# BelaExpander.net
KiCad netlist of a schematic drawn in EAGLE
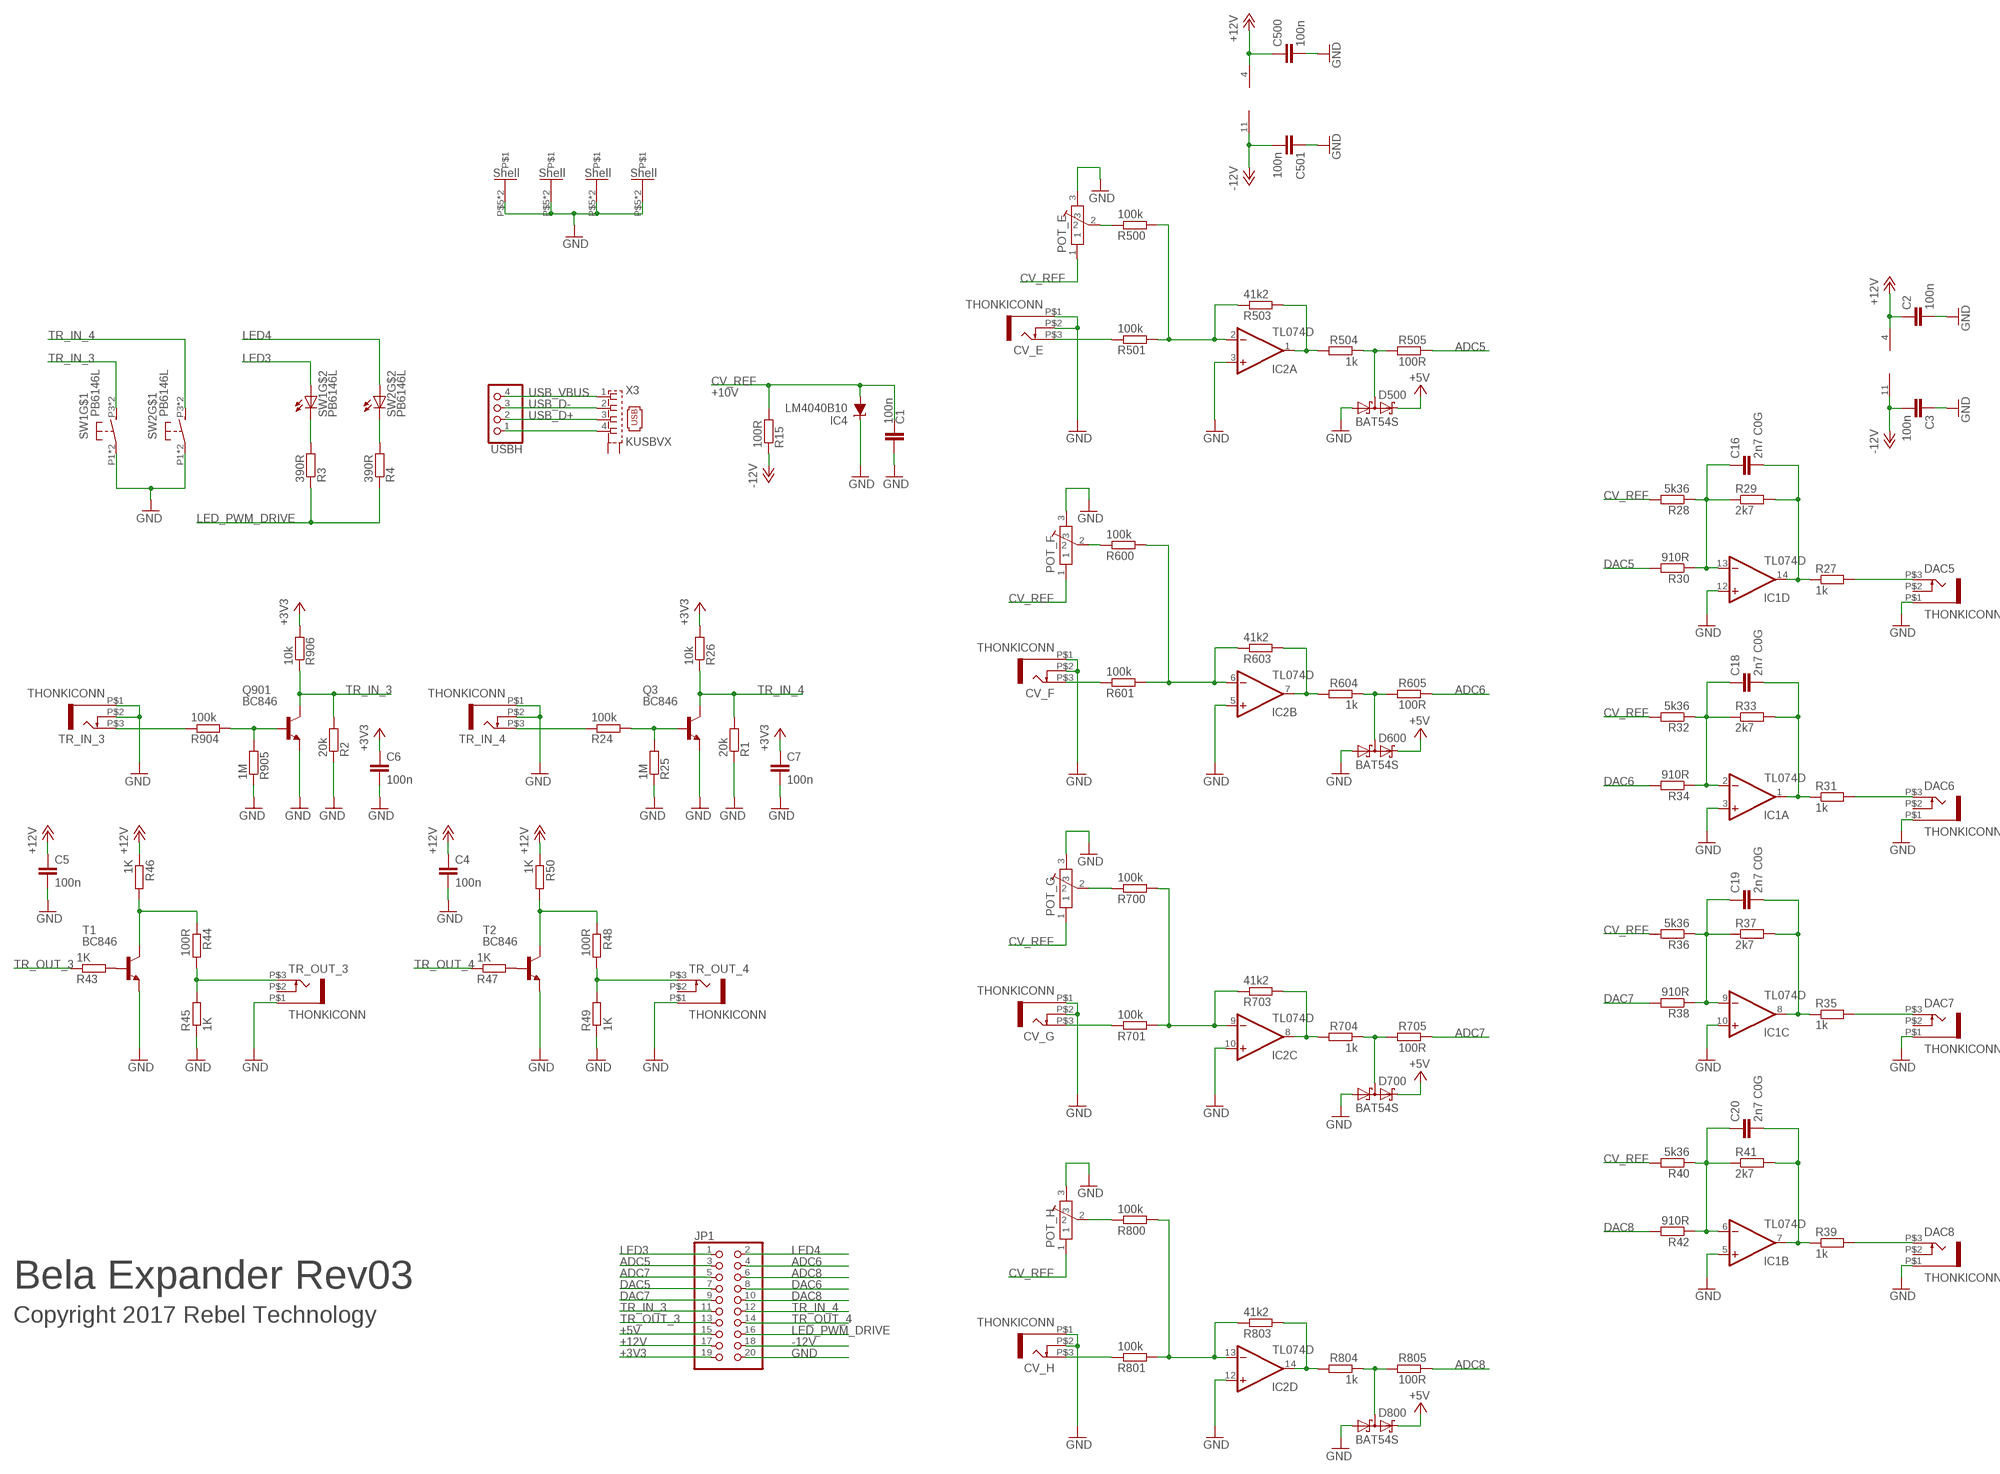
[diagram p0: schematic, sheet 1]

(export (version "E")
  (design (tool "Eeschema 10.0.6"))
  (components
    (comp (ref "C1")
      (value "100n")
      (footprint "eagle-import:C0603")
      (libsource (lib "eagle-import") (part "resistor_C-EUC0603"))
    )
    (comp (ref "C2")
      (value "100n")
      (footprint "eagle-import:C0603")
      (libsource (lib "eagle-import") (part "resistor_C-EUC0603"))
    )
    (comp (ref "C3")
      (value "100n")
      (footprint "eagle-import:C0603")
      (libsource (lib "eagle-import") (part "resistor_C-EUC0603"))
    )
    (comp (ref "C4")
      (value "100n")
      (footprint "eagle-import:C0603")
      (libsource (lib "eagle-import") (part "resistor_C-EUC0603"))
    )
    (comp (ref "C5")
      (value "100n")
      (footprint "eagle-import:C0603")
      (libsource (lib "eagle-import") (part "resistor_C-EUC0603"))
    )
    (comp (ref "C6")
      (value "100n")
      (footprint "eagle-import:C0603")
      (libsource (lib "eagle-import") (part "resistor_C-EUC0603"))
    )
    (comp (ref "C7")
      (value "100n")
      (footprint "eagle-import:C0603")
      (libsource (lib "eagle-import") (part "resistor_C-EUC0603"))
    )
    (comp (ref "C16")
      (value "2n7 C0G")
      (footprint "eagle-import:C0603")
      (libsource (lib "eagle-import") (part "C-EUC0603"))
    )
    (comp (ref "C18")
      (value "2n7 C0G")
      (footprint "eagle-import:C0603")
      (libsource (lib "eagle-import") (part "C-EUC0603"))
    )
    (comp (ref "C19")
      (value "2n7 C0G")
      (footprint "eagle-import:C0603")
      (libsource (lib "eagle-import") (part "C-EUC0603"))
    )
    (comp (ref "C20")
      (value "2n7 C0G")
      (footprint "eagle-import:C0603")
      (libsource (lib "eagle-import") (part "C-EUC0603"))
    )
    (comp (ref "C500")
      (value "100n")
      (footprint "eagle-import:C0603")
      (libsource (lib "eagle-import") (part "resistor_C-EUC0603"))
    )
    (comp (ref "C501")
      (value "100n")
      (footprint "eagle-import:C0603")
      (libsource (lib "eagle-import") (part "resistor_C-EUC0603"))
    )
    (comp (ref "CV_E")
      (value "THONKICONN")
      (footprint "eagle-import:THONKICONN")
      (libsource (lib "eagle-import") (part "THONKICONN"))
    )
    (comp (ref "CV_F")
      (value "THONKICONN")
      (footprint "eagle-import:THONKICONN")
      (libsource (lib "eagle-import") (part "THONKICONN"))
    )
    (comp (ref "CV_G")
      (value "THONKICONN")
      (footprint "eagle-import:THONKICONN")
      (libsource (lib "eagle-import") (part "THONKICONN"))
    )
    (comp (ref "CV_H")
      (value "THONKICONN")
      (footprint "eagle-import:THONKICONN")
      (libsource (lib "eagle-import") (part "THONKICONN"))
    )
    (comp (ref "D500")
      (value "BAT54S")
      (footprint "eagle-import:SOT23")
      (libsource (lib "eagle-import") (part "BAT54S"))
    )
    (comp (ref "D600")
      (value "BAT54S")
      (footprint "eagle-import:SOT23")
      (libsource (lib "eagle-import") (part "BAT54S"))
    )
    (comp (ref "D700")
      (value "BAT54S")
      (footprint "eagle-import:SOT23")
      (libsource (lib "eagle-import") (part "BAT54S"))
    )
    (comp (ref "D800")
      (value "BAT54S")
      (footprint "eagle-import:SOT23")
      (libsource (lib "eagle-import") (part "BAT54S"))
    )
    (comp (ref "DAC5")
      (value "THONKICONN")
      (footprint "eagle-import:THONKICONN")
      (libsource (lib "eagle-import") (part "THONKICONN"))
    )
    (comp (ref "DAC6")
      (value "THONKICONN")
      (footprint "eagle-import:THONKICONN")
      (libsource (lib "eagle-import") (part "THONKICONN"))
    )
    (comp (ref "DAC7")
      (value "THONKICONN")
      (footprint "eagle-import:THONKICONN")
      (libsource (lib "eagle-import") (part "THONKICONN"))
    )
    (comp (ref "DAC8")
      (value "THONKICONN")
      (footprint "eagle-import:THONKICONN")
      (libsource (lib "eagle-import") (part "THONKICONN"))
    )
    (comp (ref "IC1")
      (value "TL074D")
      (footprint "eagle-import:SO14")
      (libsource (lib "eagle-import") (part "TL074D"))
    )
    (comp (ref "IC2")
      (value "TL074D")
      (footprint "eagle-import:SO14")
      (libsource (lib "eagle-import") (part "TL074D"))
    )
    (comp (ref "IC4")
      (value "LM4040B10")
      (footprint "eagle-import:DBZ_R-PDSO-G3")
      (fields (field (name "MF") "TEXAS INSTRUMENT CONNECTORS") (field (name "MPN") "LM4041C12QDBZT"))
      (libsource (lib "eagle-import") (part "LM4041DBZC12"))
    )
    (comp (ref "JP1")
      (value "PINHD-2X10")
      (footprint "eagle-import:2X10")
      (libsource (lib "eagle-import") (part "PINHD-2X10"))
    )
    (comp (ref "POT_E")
      (value "POT-ALPS-RK09L1140")
      (footprint "eagle-import:POT-ALPS-RK09L1140")
      (libsource (lib "eagle-import") (part "POT-ALPS-RK09L1140"))
    )
    (comp (ref "POT_F")
      (value "POT-ALPS-RK09L1140")
      (footprint "eagle-import:POT-ALPS-RK09L1140")
      (libsource (lib "eagle-import") (part "POT-ALPS-RK09L1140"))
    )
    (comp (ref "POT_G")
      (value "POT-ALPS-RK09L1140")
      (footprint "eagle-import:POT-ALPS-RK09L1140")
      (libsource (lib "eagle-import") (part "POT-ALPS-RK09L1140"))
    )
    (comp (ref "POT_H")
      (value "POT-ALPS-RK09L1140")
      (footprint "eagle-import:POT-ALPS-RK09L1140")
      (libsource (lib "eagle-import") (part "POT-ALPS-RK09L1140"))
    )
    (comp (ref "Q3")
      (value "BC846")
      (footprint "eagle-import:SOT23")
      (libsource (lib "eagle-import") (part "BC846"))
    )
    (comp (ref "Q901")
      (value "BC846")
      (footprint "eagle-import:SOT23")
      (libsource (lib "eagle-import") (part "BC846"))
    )
    (comp (ref "R1")
      (value "20k")
      (footprint "eagle-import:0603")
      (libsource (lib "eagle-import") (part "R-EU_0603"))
    )
    (comp (ref "R2")
      (value "20k")
      (footprint "eagle-import:0603")
      (libsource (lib "eagle-import") (part "R-EU_0603"))
    )
    (comp (ref "R3")
      (value "390R")
      (footprint "eagle-import:0603")
      (libsource (lib "eagle-import") (part "R-EU_0603"))
    )
    (comp (ref "R4")
      (value "390R")
      (footprint "eagle-import:0603")
      (libsource (lib "eagle-import") (part "R-EU_0603"))
    )
    (comp (ref "R15")
      (value "100R")
      (footprint "eagle-import:0603")
      (libsource (lib "eagle-import") (part "R-EU_0603"))
    )
    (comp (ref "R24")
      (value "100k")
      (footprint "eagle-import:0603")
      (libsource (lib "eagle-import") (part "R-EU_0603"))
    )
    (comp (ref "R25")
      (value "1M")
      (footprint "eagle-import:0603")
      (libsource (lib "eagle-import") (part "R-EU_0603"))
    )
    (comp (ref "R26")
      (value "10k")
      (footprint "eagle-import:0603")
      (libsource (lib "eagle-import") (part "R-EU_0603"))
    )
    (comp (ref "R27")
      (value "1k")
      (footprint "eagle-import:0603")
      (libsource (lib "eagle-import") (part "R-EU_0603"))
    )
    (comp (ref "R28")
      (value "5k36")
      (footprint "eagle-import:0603")
      (libsource (lib "eagle-import") (part "R-EU_0603"))
    )
    (comp (ref "R29")
      (value "2k7")
      (footprint "eagle-import:0603")
      (libsource (lib "eagle-import") (part "R-EU_0603"))
    )
    (comp (ref "R30")
      (value "910R")
      (footprint "eagle-import:0603")
      (libsource (lib "eagle-import") (part "R-EU_0603"))
    )
    (comp (ref "R31")
      (value "1k")
      (footprint "eagle-import:0603")
      (libsource (lib "eagle-import") (part "R-EU_0603"))
    )
    (comp (ref "R32")
      (value "5k36")
      (footprint "eagle-import:0603")
      (libsource (lib "eagle-import") (part "R-EU_0603"))
    )
    (comp (ref "R33")
      (value "2k7")
      (footprint "eagle-import:0603")
      (libsource (lib "eagle-import") (part "R-EU_0603"))
    )
    (comp (ref "R34")
      (value "910R")
      (footprint "eagle-import:0603")
      (libsource (lib "eagle-import") (part "R-EU_0603"))
    )
    (comp (ref "R35")
      (value "1k")
      (footprint "eagle-import:0603")
      (libsource (lib "eagle-import") (part "R-EU_0603"))
    )
    (comp (ref "R36")
      (value "5k36")
      (footprint "eagle-import:0603")
      (libsource (lib "eagle-import") (part "R-EU_0603"))
    )
    (comp (ref "R37")
      (value "2k7")
      (footprint "eagle-import:0603")
      (libsource (lib "eagle-import") (part "R-EU_0603"))
    )
    (comp (ref "R38")
      (value "910R")
      (footprint "eagle-import:0603")
      (libsource (lib "eagle-import") (part "R-EU_0603"))
    )
    (comp (ref "R39")
      (value "1k")
      (footprint "eagle-import:0603")
      (libsource (lib "eagle-import") (part "R-EU_0603"))
    )
    (comp (ref "R40")
      (value "5k36")
      (footprint "eagle-import:0603")
      (libsource (lib "eagle-import") (part "R-EU_0603"))
    )
    (comp (ref "R41")
      (value "2k7")
      (footprint "eagle-import:0603")
      (libsource (lib "eagle-import") (part "R-EU_0603"))
    )
    (comp (ref "R42")
      (value "910R")
      (footprint "eagle-import:0603")
      (libsource (lib "eagle-import") (part "R-EU_0603"))
    )
    (comp (ref "R43")
      (value "1K")
      (footprint "eagle-import:0603")
      (libsource (lib "eagle-import") (part "R-EU_0603"))
    )
    (comp (ref "R44")
      (value "100R")
      (footprint "eagle-import:0603")
      (libsource (lib "eagle-import") (part "R-EU_0603"))
    )
    (comp (ref "R45")
      (value "1K")
      (footprint "eagle-import:0603")
      (libsource (lib "eagle-import") (part "R-EU_0603"))
    )
    (comp (ref "R46")
      (value "1K")
      (footprint "eagle-import:0603")
      (libsource (lib "eagle-import") (part "R-EU_0603"))
    )
    (comp (ref "R47")
      (value "1K")
      (footprint "eagle-import:0603")
      (libsource (lib "eagle-import") (part "R-EU_0603"))
    )
    (comp (ref "R48")
      (value "100R")
      (footprint "eagle-import:0603")
      (libsource (lib "eagle-import") (part "R-EU_0603"))
    )
    (comp (ref "R49")
      (value "1K")
      (footprint "eagle-import:0603")
      (libsource (lib "eagle-import") (part "R-EU_0603"))
    )
    (comp (ref "R50")
      (value "1K")
      (footprint "eagle-import:0603")
      (libsource (lib "eagle-import") (part "R-EU_0603"))
    )
    (comp (ref "R500")
      (value "100k")
      (footprint "eagle-import:0603")
      (libsource (lib "eagle-import") (part "R-EU_0603"))
    )
    (comp (ref "R501")
      (value "100k")
      (footprint "eagle-import:0603")
      (libsource (lib "eagle-import") (part "R-EU_0603"))
    )
    (comp (ref "R503")
      (value "41k2")
      (footprint "eagle-import:0603")
      (libsource (lib "eagle-import") (part "R-EU_0603"))
    )
    (comp (ref "R504")
      (value "1k")
      (footprint "eagle-import:0603")
      (libsource (lib "eagle-import") (part "R-EU_0603"))
    )
    (comp (ref "R505")
      (value "100R")
      (footprint "eagle-import:0603")
      (libsource (lib "eagle-import") (part "R-EU_0603"))
    )
    (comp (ref "R600")
      (value "100k")
      (footprint "eagle-import:0603")
      (libsource (lib "eagle-import") (part "R-EU_0603"))
    )
    (comp (ref "R601")
      (value "100k")
      (footprint "eagle-import:0603")
      (libsource (lib "eagle-import") (part "R-EU_0603"))
    )
    (comp (ref "R603")
      (value "41k2")
      (footprint "eagle-import:0603")
      (libsource (lib "eagle-import") (part "R-EU_0603"))
    )
    (comp (ref "R604")
      (value "1k")
      (footprint "eagle-import:0603")
      (libsource (lib "eagle-import") (part "R-EU_0603"))
    )
    (comp (ref "R605")
      (value "100R")
      (footprint "eagle-import:0603")
      (libsource (lib "eagle-import") (part "R-EU_0603"))
    )
    (comp (ref "R700")
      (value "100k")
      (footprint "eagle-import:0603")
      (libsource (lib "eagle-import") (part "R-EU_0603"))
    )
    (comp (ref "R701")
      (value "100k")
      (footprint "eagle-import:0603")
      (libsource (lib "eagle-import") (part "R-EU_0603"))
    )
    (comp (ref "R703")
      (value "41k2")
      (footprint "eagle-import:0603")
      (libsource (lib "eagle-import") (part "R-EU_0603"))
    )
    (comp (ref "R704")
      (value "1k")
      (footprint "eagle-import:0603")
      (libsource (lib "eagle-import") (part "R-EU_0603"))
    )
    (comp (ref "R705")
      (value "100R")
      (footprint "eagle-import:0603")
      (libsource (lib "eagle-import") (part "R-EU_0603"))
    )
    (comp (ref "R800")
      (value "100k")
      (footprint "eagle-import:0603")
      (libsource (lib "eagle-import") (part "R-EU_0603"))
    )
    (comp (ref "R801")
      (value "100k")
      (footprint "eagle-import:0603")
      (libsource (lib "eagle-import") (part "R-EU_0603"))
    )
    (comp (ref "R803")
      (value "41k2")
      (footprint "eagle-import:0603")
      (libsource (lib "eagle-import") (part "R-EU_0603"))
    )
    (comp (ref "R804")
      (value "1k")
      (footprint "eagle-import:0603")
      (libsource (lib "eagle-import") (part "R-EU_0603"))
    )
    (comp (ref "R805")
      (value "100R")
      (footprint "eagle-import:0603")
      (libsource (lib "eagle-import") (part "R-EU_0603"))
    )
    (comp (ref "R904")
      (value "100k")
      (footprint "eagle-import:0603")
      (libsource (lib "eagle-import") (part "R-EU_0603"))
    )
    (comp (ref "R905")
      (value "1M")
      (footprint "eagle-import:0603")
      (libsource (lib "eagle-import") (part "R-EU_0603"))
    )
    (comp (ref "R906")
      (value "10k")
      (footprint "eagle-import:0603")
      (libsource (lib "eagle-import") (part "R-EU_0603"))
    )
    (comp (ref "SW1")
      (value "PB6146L")
      (footprint "eagle-import:PB6146L")
      (libsource (lib "eagle-import") (part "PB6146L"))
    )
    (comp (ref "SW2")
      (value "PB6146L")
      (footprint "eagle-import:PB6146L")
      (libsource (lib "eagle-import") (part "PB6146L"))
    )
    (comp (ref "T1")
      (value "BC846")
      (footprint "eagle-import:SOT23")
      (libsource (lib "eagle-import") (part "BC846"))
    )
    (comp (ref "T2")
      (value "BC846")
      (footprint "eagle-import:SOT23")
      (libsource (lib "eagle-import") (part "BC846"))
    )
    (comp (ref "TR_IN_3")
      (value "THONKICONN")
      (footprint "eagle-import:THONKICONN")
      (libsource (lib "eagle-import") (part "THONKICONN"))
    )
    (comp (ref "TR_IN_4")
      (value "THONKICONN")
      (footprint "eagle-import:THONKICONN")
      (libsource (lib "eagle-import") (part "THONKICONN"))
    )
    (comp (ref "TR_OUT_3")
      (value "THONKICONN")
      (footprint "eagle-import:THONKICONN")
      (libsource (lib "eagle-import") (part "THONKICONN"))
    )
    (comp (ref "TR_OUT_4")
      (value "THONKICONN")
      (footprint "eagle-import:THONKICONN")
      (libsource (lib "eagle-import") (part "THONKICONN"))
    )
    (comp (ref "USBH")
      (value "PINHD-1X4")
      (footprint "eagle-import:1X04")
      (libsource (lib "eagle-import") (part "PINHD-1X4"))
    )
    (comp (ref "X3")
      (value "KUSBVX")
      (footprint "eagle-import:KUSBVX")
      (libsource (lib "eagle-import") (part "KUSBVX"))
    )
  )
  (nets
    (net (code "1") (name "+3V3") (class "Default")
      (node (ref "C6") (pin "1") (pinfunction "1_1") (pintype "passive"))
      (node (ref "C7") (pin "1") (pinfunction "1_1") (pintype "passive"))
      (node (ref "JP1") (pin "19") (pinfunction "19_19") (pintype "passive"))
      (node (ref "R26") (pin "2") (pinfunction "2_2") (pintype "passive"))
      (node (ref "R906") (pin "2") (pinfunction "2_2") (pintype "passive"))
    )
    (net (code "2") (name "+5V") (class "Default")
      (node (ref "D500") (pin "2") (pinfunction "C2_2") (pintype "passive"))
      (node (ref "D600") (pin "2") (pinfunction "C2_2") (pintype "passive"))
      (node (ref "D700") (pin "2") (pinfunction "C2_2") (pintype "passive"))
      (node (ref "D800") (pin "2") (pinfunction "C2_2") (pintype "passive"))
      (node (ref "JP1") (pin "15") (pinfunction "15_15") (pintype "passive"))
    )
    (net (code "3") (name "+12V") (class "Default")
      (node (ref "C2") (pin "1") (pinfunction "1_1") (pintype "passive"))
      (node (ref "C4") (pin "1") (pinfunction "1_1") (pintype "passive"))
      (node (ref "C5") (pin "1") (pinfunction "1_1") (pintype "passive"))
      (node (ref "C500") (pin "1") (pinfunction "1_1") (pintype "passive"))
      (node (ref "IC1") (pin "4") (pinfunction "V+_4") (pintype "power_in"))
      (node (ref "IC2") (pin "4") (pinfunction "V+_4") (pintype "power_in"))
      (node (ref "JP1") (pin "17") (pinfunction "17_17") (pintype "passive"))
      (node (ref "R46") (pin "1") (pinfunction "1_1") (pintype "passive"))
      (node (ref "R50") (pin "1") (pinfunction "1_1") (pintype "passive"))
    )
    (net (code "4") (name "-12V") (class "Default")
      (node (ref "C3") (pin "2") (pinfunction "2_2") (pintype "passive"))
      (node (ref "C501") (pin "2") (pinfunction "2_2") (pintype "passive"))
      (node (ref "IC1") (pin "11") (pinfunction "V-_11") (pintype "power_in"))
      (node (ref "IC2") (pin "11") (pinfunction "V-_11") (pintype "power_in"))
      (node (ref "JP1") (pin "18") (pinfunction "18_18") (pintype "passive"))
      (node (ref "R15") (pin "1") (pinfunction "1_1") (pintype "passive"))
    )
    (net (code "5") (name "/ADC5") (class "Default")
      (node (ref "JP1") (pin "3") (pinfunction "3_3") (pintype "passive"))
      (node (ref "R505") (pin "1") (pinfunction "1_1") (pintype "passive"))
    )
    (net (code "6") (name "/ADC6") (class "Default")
      (node (ref "JP1") (pin "4") (pinfunction "4_4") (pintype "passive"))
      (node (ref "R605") (pin "1") (pinfunction "1_1") (pintype "passive"))
    )
    (net (code "7") (name "/ADC7") (class "Default")
      (node (ref "JP1") (pin "5") (pinfunction "5_5") (pintype "passive"))
      (node (ref "R705") (pin "1") (pinfunction "1_1") (pintype "passive"))
    )
    (net (code "8") (name "/ADC8") (class "Default")
      (node (ref "JP1") (pin "6") (pinfunction "6_6") (pintype "passive"))
      (node (ref "R805") (pin "1") (pinfunction "1_1") (pintype "passive"))
    )
    (net (code "9") (name "/CV_REF") (class "Default")
      (node (ref "C1") (pin "1") (pinfunction "1_1") (pintype "passive"))
      (node (ref "IC4") (pin "2") (pinfunction "A_2") (pintype "passive"))
      (node (ref "POT_E") (pin "1") (pinfunction "1_1") (pintype "bidirectional"))
      (node (ref "POT_F") (pin "1") (pinfunction "1_1") (pintype "bidirectional"))
      (node (ref "POT_G") (pin "1") (pinfunction "1_1") (pintype "bidirectional"))
      (node (ref "POT_H") (pin "1") (pinfunction "1_1") (pintype "bidirectional"))
      (node (ref "R15") (pin "2") (pinfunction "2_2") (pintype "passive"))
      (node (ref "R28") (pin "2") (pinfunction "2_2") (pintype "passive"))
      (node (ref "R32") (pin "2") (pinfunction "2_2") (pintype "passive"))
      (node (ref "R36") (pin "2") (pinfunction "2_2") (pintype "passive"))
      (node (ref "R40") (pin "2") (pinfunction "2_2") (pintype "passive"))
    )
    (net (code "10") (name "/DAC5") (class "Default")
      (node (ref "JP1") (pin "7") (pinfunction "7_7") (pintype "passive"))
      (node (ref "R30") (pin "2") (pinfunction "2_2") (pintype "passive"))
    )
    (net (code "11") (name "/DAC6") (class "Default")
      (node (ref "JP1") (pin "8") (pinfunction "8_8") (pintype "passive"))
      (node (ref "R34") (pin "2") (pinfunction "2_2") (pintype "passive"))
    )
    (net (code "12") (name "/DAC7") (class "Default")
      (node (ref "JP1") (pin "9") (pinfunction "9_9") (pintype "passive"))
      (node (ref "R38") (pin "2") (pinfunction "2_2") (pintype "passive"))
    )
    (net (code "13") (name "/DAC8") (class "Default")
      (node (ref "JP1") (pin "10") (pinfunction "10_10") (pintype "passive"))
      (node (ref "R42") (pin "2") (pinfunction "2_2") (pintype "passive"))
    )
    (net (code "14") (name "/LED3") (class "Default")
      (node (ref "JP1") (pin "1") (pinfunction "1_1") (pintype "passive"))
      (node (ref "SW1") (pin "PL1") (pinfunction "A_PL1") (pintype "passive"))
    )
    (net (code "15") (name "/LED4") (class "Default")
      (node (ref "JP1") (pin "2") (pinfunction "2_2") (pintype "passive"))
      (node (ref "SW2") (pin "PL1") (pinfunction "A_PL1") (pintype "passive"))
    )
    (net (code "16") (name "/LED_PWM_DRIVE") (class "Default")
      (node (ref "JP1") (pin "16") (pinfunction "16_16") (pintype "passive"))
      (node (ref "R3") (pin "1") (pinfunction "1_1") (pintype "passive"))
      (node (ref "R4") (pin "1") (pinfunction "1_1") (pintype "passive"))
    )
    (net (code "17") (name "/TR_IN_3") (class "Default")
      (node (ref "JP1") (pin "11") (pinfunction "11_11") (pintype "passive"))
      (node (ref "Q901") (pin "3") (pinfunction "C_3") (pintype "passive"))
      (node (ref "R2") (pin "2") (pinfunction "2_2") (pintype "passive"))
      (node (ref "R906") (pin "1") (pinfunction "1_1") (pintype "passive"))
      (node (ref "SW1") (pin "P3") (pinfunction "S_P3") (pintype "passive"))
      (node (ref "SW1") (pin "P4") (pinfunction "S_P4") (pintype "passive"))
    )
    (net (code "18") (name "/TR_IN_4") (class "Default")
      (node (ref "JP1") (pin "12") (pinfunction "12_12") (pintype "passive"))
      (node (ref "Q3") (pin "3") (pinfunction "C_3") (pintype "passive"))
      (node (ref "R1") (pin "2") (pinfunction "2_2") (pintype "passive"))
      (node (ref "R26") (pin "1") (pinfunction "1_1") (pintype "passive"))
      (node (ref "SW2") (pin "P3") (pinfunction "S_P3") (pintype "passive"))
      (node (ref "SW2") (pin "P4") (pinfunction "S_P4") (pintype "passive"))
    )
    (net (code "19") (name "/TR_OUT_3") (class "Default")
      (node (ref "JP1") (pin "13") (pinfunction "13_13") (pintype "passive"))
      (node (ref "R43") (pin "1") (pinfunction "1_1") (pintype "passive"))
    )
    (net (code "20") (name "/TR_OUT_4") (class "Default")
      (node (ref "JP1") (pin "14") (pinfunction "14_14") (pintype "passive"))
      (node (ref "R47") (pin "1") (pinfunction "1_1") (pintype "passive"))
    )
    (net (code "21") (name "/USB_D+") (class "Default")
      (node (ref "USBH") (pin "2") (pinfunction "2_2") (pintype "passive"))
      (node (ref "X3") (pin "3") (pinfunction "3_3") (pintype "passive"))
    )
    (net (code "22") (name "/USB_D-") (class "Default")
      (node (ref "USBH") (pin "3") (pinfunction "3_3") (pintype "passive"))
      (node (ref "X3") (pin "2") (pinfunction "2_2") (pintype "passive"))
    )
    (net (code "23") (name "/USB_VBUS") (class "Default")
      (node (ref "USBH") (pin "4") (pinfunction "4_4") (pintype "passive"))
      (node (ref "X3") (pin "1") (pinfunction "1_1") (pintype "passive"))
    )
    (net (code "24") (name "GND") (class "Default")
      (node (ref "C1") (pin "2") (pinfunction "2_2") (pintype "passive"))
      (node (ref "C2") (pin "2") (pinfunction "2_2") (pintype "passive"))
      (node (ref "C3") (pin "1") (pinfunction "1_1") (pintype "passive"))
      (node (ref "C4") (pin "2") (pinfunction "2_2") (pintype "passive"))
      (node (ref "C5") (pin "2") (pinfunction "2_2") (pintype "passive"))
      (node (ref "C500") (pin "2") (pinfunction "2_2") (pintype "passive"))
      (node (ref "C501") (pin "1") (pinfunction "1_1") (pintype "passive"))
      (node (ref "C6") (pin "2") (pinfunction "2_2") (pintype "passive"))
      (node (ref "C7") (pin "2") (pinfunction "2_2") (pintype "passive"))
      (node (ref "CV_E") (pin "P$1") (pinfunction "5_P$1") (pintype "passive"))
      (node (ref "CV_E") (pin "P$2") (pinfunction "4_P$2") (pintype "passive"))
      (node (ref "CV_F") (pin "P$1") (pinfunction "5_P$1") (pintype "passive"))
      (node (ref "CV_F") (pin "P$2") (pinfunction "4_P$2") (pintype "passive"))
      (node (ref "CV_G") (pin "P$1") (pinfunction "5_P$1") (pintype "passive"))
      (node (ref "CV_G") (pin "P$2") (pinfunction "4_P$2") (pintype "passive"))
      (node (ref "CV_H") (pin "P$1") (pinfunction "5_P$1") (pintype "passive"))
      (node (ref "CV_H") (pin "P$2") (pinfunction "4_P$2") (pintype "passive"))
      (node (ref "D500") (pin "1") (pinfunction "A1_1") (pintype "passive"))
      (node (ref "D600") (pin "1") (pinfunction "A1_1") (pintype "passive"))
      (node (ref "D700") (pin "1") (pinfunction "A1_1") (pintype "passive"))
      (node (ref "D800") (pin "1") (pinfunction "A1_1") (pintype "passive"))
      (node (ref "DAC5") (pin "P$1") (pinfunction "5_P$1") (pintype "passive"))
      (node (ref "DAC6") (pin "P$1") (pinfunction "5_P$1") (pintype "passive"))
      (node (ref "DAC7") (pin "P$1") (pinfunction "5_P$1") (pintype "passive"))
      (node (ref "DAC8") (pin "P$1") (pinfunction "5_P$1") (pintype "passive"))
      (node (ref "IC1") (pin "10") (pinfunction "+IN_10") (pintype "input"))
      (node (ref "IC1") (pin "12") (pinfunction "+IN_12") (pintype "input"))
      (node (ref "IC1") (pin "3") (pinfunction "+IN_3") (pintype "input"))
      (node (ref "IC1") (pin "5") (pinfunction "+IN_5") (pintype "input"))
      (node (ref "IC2") (pin "10") (pinfunction "+IN_10") (pintype "input"))
      (node (ref "IC2") (pin "12") (pinfunction "+IN_12") (pintype "input"))
      (node (ref "IC2") (pin "3") (pinfunction "+IN_3") (pintype "input"))
      (node (ref "IC2") (pin "5") (pinfunction "+IN_5") (pintype "input"))
      (node (ref "IC4") (pin "1") (pinfunction "C_1") (pintype "passive"))
      (node (ref "JP1") (pin "20") (pinfunction "20_20") (pintype "passive"))
      (node (ref "POT_E") (pin "3") (pinfunction "3_3") (pintype "bidirectional"))
      (node (ref "POT_E") (pin "P$5") (pinfunction "P$1_P$5") (pintype "bidirectional"))
      (node (ref "POT_E") (pin "P$6") (pinfunction "P$1_P$6") (pintype "bidirectional"))
      (node (ref "POT_F") (pin "3") (pinfunction "3_3") (pintype "bidirectional"))
      (node (ref "POT_F") (pin "P$5") (pinfunction "P$1_P$5") (pintype "bidirectional"))
      (node (ref "POT_F") (pin "P$6") (pinfunction "P$1_P$6") (pintype "bidirectional"))
      (node (ref "POT_G") (pin "3") (pinfunction "3_3") (pintype "bidirectional"))
      (node (ref "POT_G") (pin "P$5") (pinfunction "P$1_P$5") (pintype "bidirectional"))
      (node (ref "POT_G") (pin "P$6") (pinfunction "P$1_P$6") (pintype "bidirectional"))
      (node (ref "POT_H") (pin "3") (pinfunction "3_3") (pintype "bidirectional"))
      (node (ref "POT_H") (pin "P$5") (pinfunction "P$1_P$5") (pintype "bidirectional"))
      (node (ref "POT_H") (pin "P$6") (pinfunction "P$1_P$6") (pintype "bidirectional"))
      (node (ref "Q3") (pin "2") (pinfunction "E_2") (pintype "passive"))
      (node (ref "Q901") (pin "2") (pinfunction "E_2") (pintype "passive"))
      (node (ref "R1") (pin "1") (pinfunction "1_1") (pintype "passive"))
      (node (ref "R2") (pin "1") (pinfunction "1_1") (pintype "passive"))
      (node (ref "R25") (pin "1") (pinfunction "1_1") (pintype "passive"))
      (node (ref "R45") (pin "1") (pinfunction "1_1") (pintype "passive"))
      (node (ref "R49") (pin "1") (pinfunction "1_1") (pintype "passive"))
      (node (ref "R905") (pin "1") (pinfunction "1_1") (pintype "passive"))
      (node (ref "SW1") (pin "P1") (pinfunction "P_P1") (pintype "passive"))
      (node (ref "SW1") (pin "P2") (pinfunction "P_P2") (pintype "passive"))
      (node (ref "SW2") (pin "P1") (pinfunction "P_P1") (pintype "passive"))
      (node (ref "SW2") (pin "P2") (pinfunction "P_P2") (pintype "passive"))
      (node (ref "T1") (pin "2") (pinfunction "E_2") (pintype "passive"))
      (node (ref "T2") (pin "2") (pinfunction "E_2") (pintype "passive"))
      (node (ref "TR_IN_3") (pin "P$1") (pinfunction "5_P$1") (pintype "passive"))
      (node (ref "TR_IN_3") (pin "P$2") (pinfunction "4_P$2") (pintype "passive"))
      (node (ref "TR_IN_4") (pin "P$1") (pinfunction "5_P$1") (pintype "passive"))
      (node (ref "TR_IN_4") (pin "P$2") (pinfunction "4_P$2") (pintype "passive"))
      (node (ref "TR_OUT_3") (pin "P$1") (pinfunction "5_P$1") (pintype "passive"))
      (node (ref "TR_OUT_4") (pin "P$1") (pinfunction "5_P$1") (pintype "passive"))
    )
    (net (code "25") (name "Net-(CV_E-3)") (class "Default")
      (node (ref "CV_E") (pin "P$3") (pinfunction "3_P$3") (pintype "passive"))
      (node (ref "R501") (pin "1") (pinfunction "1_1") (pintype "passive"))
    )
    (net (code "26") (name "Net-(CV_F-3)") (class "Default")
      (node (ref "CV_F") (pin "P$3") (pinfunction "3_P$3") (pintype "passive"))
      (node (ref "R601") (pin "1") (pinfunction "1_1") (pintype "passive"))
    )
    (net (code "27") (name "Net-(CV_G-3)") (class "Default")
      (node (ref "CV_G") (pin "P$3") (pinfunction "3_P$3") (pintype "passive"))
      (node (ref "R701") (pin "1") (pinfunction "1_1") (pintype "passive"))
    )
    (net (code "28") (name "Net-(CV_H-3)") (class "Default")
      (node (ref "CV_H") (pin "P$3") (pinfunction "3_P$3") (pintype "passive"))
      (node (ref "R801") (pin "1") (pinfunction "1_1") (pintype "passive"))
    )
    (net (code "29") (name "Net-(D500-C1A2)") (class "Default")
      (node (ref "D500") (pin "3") (pinfunction "C1A2_3") (pintype "passive"))
      (node (ref "R504") (pin "1") (pinfunction "1_1") (pintype "passive"))
      (node (ref "R505") (pin "2") (pinfunction "2_2") (pintype "passive"))
    )
    (net (code "30") (name "Net-(D600-C1A2)") (class "Default")
      (node (ref "D600") (pin "3") (pinfunction "C1A2_3") (pintype "passive"))
      (node (ref "R604") (pin "1") (pinfunction "1_1") (pintype "passive"))
      (node (ref "R605") (pin "2") (pinfunction "2_2") (pintype "passive"))
    )
    (net (code "31") (name "Net-(D700-C1A2)") (class "Default")
      (node (ref "D700") (pin "3") (pinfunction "C1A2_3") (pintype "passive"))
      (node (ref "R704") (pin "1") (pinfunction "1_1") (pintype "passive"))
      (node (ref "R705") (pin "2") (pinfunction "2_2") (pintype "passive"))
    )
    (net (code "32") (name "Net-(D800-C1A2)") (class "Default")
      (node (ref "D800") (pin "3") (pinfunction "C1A2_3") (pintype "passive"))
      (node (ref "R804") (pin "1") (pinfunction "1_1") (pintype "passive"))
      (node (ref "R805") (pin "2") (pinfunction "2_2") (pintype "passive"))
    )
    (net (code "33") (name "Net-(DAC5-3)") (class "Default")
      (node (ref "DAC5") (pin "P$3") (pinfunction "3_P$3") (pintype "passive"))
      (node (ref "R27") (pin "2") (pinfunction "2_2") (pintype "passive"))
    )
    (net (code "34") (name "Net-(DAC6-3)") (class "Default")
      (node (ref "DAC6") (pin "P$3") (pinfunction "3_P$3") (pintype "passive"))
      (node (ref "R31") (pin "2") (pinfunction "2_2") (pintype "passive"))
    )
    (net (code "35") (name "Net-(DAC7-3)") (class "Default")
      (node (ref "DAC7") (pin "P$3") (pinfunction "3_P$3") (pintype "passive"))
      (node (ref "R35") (pin "2") (pinfunction "2_2") (pintype "passive"))
    )
    (net (code "36") (name "Net-(DAC8-3)") (class "Default")
      (node (ref "DAC8") (pin "P$3") (pinfunction "3_P$3") (pintype "passive"))
      (node (ref "R39") (pin "2") (pinfunction "2_2") (pintype "passive"))
    )
    (net (code "37") (name "Net-(IC1A--IN)") (class "Default")
      (node (ref "C18") (pin "1") (pinfunction "1_1") (pintype "passive"))
      (node (ref "IC1") (pin "2") (pinfunction "-IN_2") (pintype "input"))
      (node (ref "R32") (pin "1") (pinfunction "1_1") (pintype "passive"))
      (node (ref "R33") (pin "1") (pinfunction "1_1") (pintype "passive"))
      (node (ref "R34") (pin "1") (pinfunction "1_1") (pintype "passive"))
    )
    (net (code "38") (name "Net-(IC1A-OUT)") (class "Default")
      (node (ref "C18") (pin "2") (pinfunction "2_2") (pintype "passive"))
      (node (ref "IC1") (pin "1") (pinfunction "OUT_1") (pintype "output"))
      (node (ref "R31") (pin "1") (pinfunction "1_1") (pintype "passive"))
      (node (ref "R33") (pin "2") (pinfunction "2_2") (pintype "passive"))
    )
    (net (code "39") (name "Net-(IC1B--IN)") (class "Default")
      (node (ref "C20") (pin "1") (pinfunction "1_1") (pintype "passive"))
      (node (ref "IC1") (pin "6") (pinfunction "-IN_6") (pintype "input"))
      (node (ref "R40") (pin "1") (pinfunction "1_1") (pintype "passive"))
      (node (ref "R41") (pin "1") (pinfunction "1_1") (pintype "passive"))
      (node (ref "R42") (pin "1") (pinfunction "1_1") (pintype "passive"))
    )
    (net (code "40") (name "Net-(IC1B-OUT)") (class "Default")
      (node (ref "C20") (pin "2") (pinfunction "2_2") (pintype "passive"))
      (node (ref "IC1") (pin "7") (pinfunction "OUT_7") (pintype "output"))
      (node (ref "R39") (pin "1") (pinfunction "1_1") (pintype "passive"))
      (node (ref "R41") (pin "2") (pinfunction "2_2") (pintype "passive"))
    )
    (net (code "41") (name "Net-(IC1C--IN)") (class "Default")
      (node (ref "C19") (pin "1") (pinfunction "1_1") (pintype "passive"))
      (node (ref "IC1") (pin "9") (pinfunction "-IN_9") (pintype "input"))
      (node (ref "R36") (pin "1") (pinfunction "1_1") (pintype "passive"))
      (node (ref "R37") (pin "1") (pinfunction "1_1") (pintype "passive"))
      (node (ref "R38") (pin "1") (pinfunction "1_1") (pintype "passive"))
    )
    (net (code "42") (name "Net-(IC1C-OUT)") (class "Default")
      (node (ref "C19") (pin "2") (pinfunction "2_2") (pintype "passive"))
      (node (ref "IC1") (pin "8") (pinfunction "OUT_8") (pintype "output"))
      (node (ref "R35") (pin "1") (pinfunction "1_1") (pintype "passive"))
      (node (ref "R37") (pin "2") (pinfunction "2_2") (pintype "passive"))
    )
    (net (code "43") (name "Net-(IC1D--IN)") (class "Default")
      (node (ref "C16") (pin "1") (pinfunction "1_1") (pintype "passive"))
      (node (ref "IC1") (pin "13") (pinfunction "-IN_13") (pintype "input"))
      (node (ref "R28") (pin "1") (pinfunction "1_1") (pintype "passive"))
      (node (ref "R29") (pin "1") (pinfunction "1_1") (pintype "passive"))
      (node (ref "R30") (pin "1") (pinfunction "1_1") (pintype "passive"))
    )
    (net (code "44") (name "Net-(IC1D-OUT)") (class "Default")
      (node (ref "C16") (pin "2") (pinfunction "2_2") (pintype "passive"))
      (node (ref "IC1") (pin "14") (pinfunction "OUT_14") (pintype "output"))
      (node (ref "R27") (pin "1") (pinfunction "1_1") (pintype "passive"))
      (node (ref "R29") (pin "2") (pinfunction "2_2") (pintype "passive"))
    )
    (net (code "45") (name "Net-(IC2A--IN)") (class "Default")
      (node (ref "IC2") (pin "2") (pinfunction "-IN_2") (pintype "input"))
      (node (ref "R500") (pin "2") (pinfunction "2_2") (pintype "passive"))
      (node (ref "R501") (pin "2") (pinfunction "2_2") (pintype "passive"))
      (node (ref "R503") (pin "1") (pinfunction "1_1") (pintype "passive"))
    )
    (net (code "46") (name "Net-(IC2A-OUT)") (class "Default")
      (node (ref "IC2") (pin "1") (pinfunction "OUT_1") (pintype "output"))
      (node (ref "R503") (pin "2") (pinfunction "2_2") (pintype "passive"))
      (node (ref "R504") (pin "2") (pinfunction "2_2") (pintype "passive"))
    )
    (net (code "47") (name "Net-(IC2B--IN)") (class "Default")
      (node (ref "IC2") (pin "6") (pinfunction "-IN_6") (pintype "input"))
      (node (ref "R600") (pin "2") (pinfunction "2_2") (pintype "passive"))
      (node (ref "R601") (pin "2") (pinfunction "2_2") (pintype "passive"))
      (node (ref "R603") (pin "1") (pinfunction "1_1") (pintype "passive"))
    )
    (net (code "48") (name "Net-(IC2B-OUT)") (class "Default")
      (node (ref "IC2") (pin "7") (pinfunction "OUT_7") (pintype "output"))
      (node (ref "R603") (pin "2") (pinfunction "2_2") (pintype "passive"))
      (node (ref "R604") (pin "2") (pinfunction "2_2") (pintype "passive"))
    )
    (net (code "49") (name "Net-(IC2C--IN)") (class "Default")
      (node (ref "IC2") (pin "9") (pinfunction "-IN_9") (pintype "input"))
      (node (ref "R700") (pin "2") (pinfunction "2_2") (pintype "passive"))
      (node (ref "R701") (pin "2") (pinfunction "2_2") (pintype "passive"))
      (node (ref "R703") (pin "1") (pinfunction "1_1") (pintype "passive"))
    )
    (net (code "50") (name "Net-(IC2C-OUT)") (class "Default")
      (node (ref "IC2") (pin "8") (pinfunction "OUT_8") (pintype "output"))
      (node (ref "R703") (pin "2") (pinfunction "2_2") (pintype "passive"))
      (node (ref "R704") (pin "2") (pinfunction "2_2") (pintype "passive"))
    )
    (net (code "51") (name "Net-(IC2D--IN)") (class "Default")
      (node (ref "IC2") (pin "13") (pinfunction "-IN_13") (pintype "input"))
      (node (ref "R800") (pin "2") (pinfunction "2_2") (pintype "passive"))
      (node (ref "R801") (pin "2") (pinfunction "2_2") (pintype "passive"))
      (node (ref "R803") (pin "1") (pinfunction "1_1") (pintype "passive"))
    )
    (net (code "52") (name "Net-(IC2D-OUT)") (class "Default")
      (node (ref "IC2") (pin "14") (pinfunction "OUT_14") (pintype "output"))
      (node (ref "R803") (pin "2") (pinfunction "2_2") (pintype "passive"))
      (node (ref "R804") (pin "2") (pinfunction "2_2") (pintype "passive"))
    )
    (net (code "53") (name "Net-(POT_E-Pad2)") (class "Default")
      (node (ref "POT_E") (pin "2") (pinfunction "2_2") (pintype "bidirectional"))
      (node (ref "R500") (pin "1") (pinfunction "1_1") (pintype "passive"))
    )
    (net (code "54") (name "Net-(POT_F-Pad2)") (class "Default")
      (node (ref "POT_F") (pin "2") (pinfunction "2_2") (pintype "bidirectional"))
      (node (ref "R600") (pin "1") (pinfunction "1_1") (pintype "passive"))
    )
    (net (code "55") (name "Net-(POT_G-Pad2)") (class "Default")
      (node (ref "POT_G") (pin "2") (pinfunction "2_2") (pintype "bidirectional"))
      (node (ref "R700") (pin "1") (pinfunction "1_1") (pintype "passive"))
    )
    (net (code "56") (name "Net-(POT_H-Pad2)") (class "Default")
      (node (ref "POT_H") (pin "2") (pinfunction "2_2") (pintype "bidirectional"))
      (node (ref "R800") (pin "1") (pinfunction "1_1") (pintype "passive"))
    )
    (net (code "57") (name "Net-(Q3-B)") (class "Default")
      (node (ref "Q3") (pin "1") (pinfunction "B_1") (pintype "passive"))
      (node (ref "R24") (pin "2") (pinfunction "2_2") (pintype "passive"))
      (node (ref "R25") (pin "2") (pinfunction "2_2") (pintype "passive"))
    )
    (net (code "58") (name "Net-(Q901-B)") (class "Default")
      (node (ref "Q901") (pin "1") (pinfunction "B_1") (pintype "passive"))
      (node (ref "R904") (pin "2") (pinfunction "2_2") (pintype "passive"))
      (node (ref "R905") (pin "2") (pinfunction "2_2") (pintype "passive"))
    )
    (net (code "59") (name "Net-(SW1B-C)") (class "Default")
      (node (ref "R3") (pin "2") (pinfunction "2_2") (pintype "passive"))
      (node (ref "SW1") (pin "PL2") (pinfunction "C_PL2") (pintype "passive"))
    )
    (net (code "60") (name "Net-(SW2B-C)") (class "Default")
      (node (ref "R4") (pin "2") (pinfunction "2_2") (pintype "passive"))
      (node (ref "SW2") (pin "PL2") (pinfunction "C_PL2") (pintype "passive"))
    )
    (net (code "61") (name "Net-(T1-B)") (class "Default")
      (node (ref "R43") (pin "2") (pinfunction "2_2") (pintype "passive"))
      (node (ref "T1") (pin "1") (pinfunction "B_1") (pintype "passive"))
    )
    (net (code "62") (name "Net-(T1-C)") (class "Default")
      (node (ref "R44") (pin "1") (pinfunction "1_1") (pintype "passive"))
      (node (ref "R46") (pin "2") (pinfunction "2_2") (pintype "passive"))
      (node (ref "T1") (pin "3") (pinfunction "C_3") (pintype "passive"))
    )
    (net (code "63") (name "Net-(T2-B)") (class "Default")
      (node (ref "R47") (pin "2") (pinfunction "2_2") (pintype "passive"))
      (node (ref "T2") (pin "1") (pinfunction "B_1") (pintype "passive"))
    )
    (net (code "64") (name "Net-(T2-C)") (class "Default")
      (node (ref "R48") (pin "1") (pinfunction "1_1") (pintype "passive"))
      (node (ref "R50") (pin "2") (pinfunction "2_2") (pintype "passive"))
      (node (ref "T2") (pin "3") (pinfunction "C_3") (pintype "passive"))
    )
    (net (code "65") (name "Net-(TR_IN_3-3)") (class "Default")
      (node (ref "R904") (pin "1") (pinfunction "1_1") (pintype "passive"))
      (node (ref "TR_IN_3") (pin "P$3") (pinfunction "3_P$3") (pintype "passive"))
    )
    (net (code "66") (name "Net-(TR_IN_4-3)") (class "Default")
      (node (ref "R24") (pin "1") (pinfunction "1_1") (pintype "passive"))
      (node (ref "TR_IN_4") (pin "P$3") (pinfunction "3_P$3") (pintype "passive"))
    )
    (net (code "67") (name "Net-(TR_OUT_3-3)") (class "Default")
      (node (ref "R44") (pin "2") (pinfunction "2_2") (pintype "passive"))
      (node (ref "R45") (pin "2") (pinfunction "2_2") (pintype "passive"))
      (node (ref "TR_OUT_3") (pin "P$3") (pinfunction "3_P$3") (pintype "passive"))
    )
    (net (code "68") (name "Net-(TR_OUT_4-3)") (class "Default")
      (node (ref "R48") (pin "2") (pinfunction "2_2") (pintype "passive"))
      (node (ref "R49") (pin "2") (pinfunction "2_2") (pintype "passive"))
      (node (ref "TR_OUT_4") (pin "P$3") (pinfunction "3_P$3") (pintype "passive"))
    )
    (net (code "69") (name "Net-(USBH-Pad1)") (class "Default")
      (node (ref "USBH") (pin "1") (pinfunction "1_1") (pintype "passive"))
      (node (ref "X3") (pin "4") (pinfunction "4_4") (pintype "passive"))
    )
    (net (code "70") (name "unconnected-(DAC5-4-PadP$2)") (class "Default")
      (node (ref "DAC5") (pin "P$2") (pinfunction "4_P$2") (pintype "passive"))
    )
    (net (code "71") (name "unconnected-(DAC6-4-PadP$2)") (class "Default")
      (node (ref "DAC6") (pin "P$2") (pinfunction "4_P$2") (pintype "passive"))
    )
    (net (code "72") (name "unconnected-(DAC7-4-PadP$2)") (class "Default")
      (node (ref "DAC7") (pin "P$2") (pinfunction "4_P$2") (pintype "passive"))
    )
    (net (code "73") (name "unconnected-(DAC8-4-PadP$2)") (class "Default")
      (node (ref "DAC8") (pin "P$2") (pinfunction "4_P$2") (pintype "passive"))
    )
    (net (code "74") (name "unconnected-(TR_OUT_3-4-PadP$2)") (class "Default")
      (node (ref "TR_OUT_3") (pin "P$2") (pinfunction "4_P$2") (pintype "passive"))
    )
    (net (code "75") (name "unconnected-(TR_OUT_4-4-PadP$2)") (class "Default")
      (node (ref "TR_OUT_4") (pin "P$2") (pinfunction "4_P$2") (pintype "passive"))
    )
    (net (code "76") (name "unconnected-(X3-S1-PadM1)") (class "Default")
      (node (ref "X3") (pin "M1") (pinfunction "S1_M1") (pintype "passive"))
    )
    (net (code "77") (name "unconnected-(X3-S2-PadM2)") (class "Default")
      (node (ref "X3") (pin "M2") (pinfunction "S2_M2") (pintype "passive"))
    )
  )
)
